# RGB_sensro_schematic.net
KiCad netlist of a schematic drawn in Altium Designer
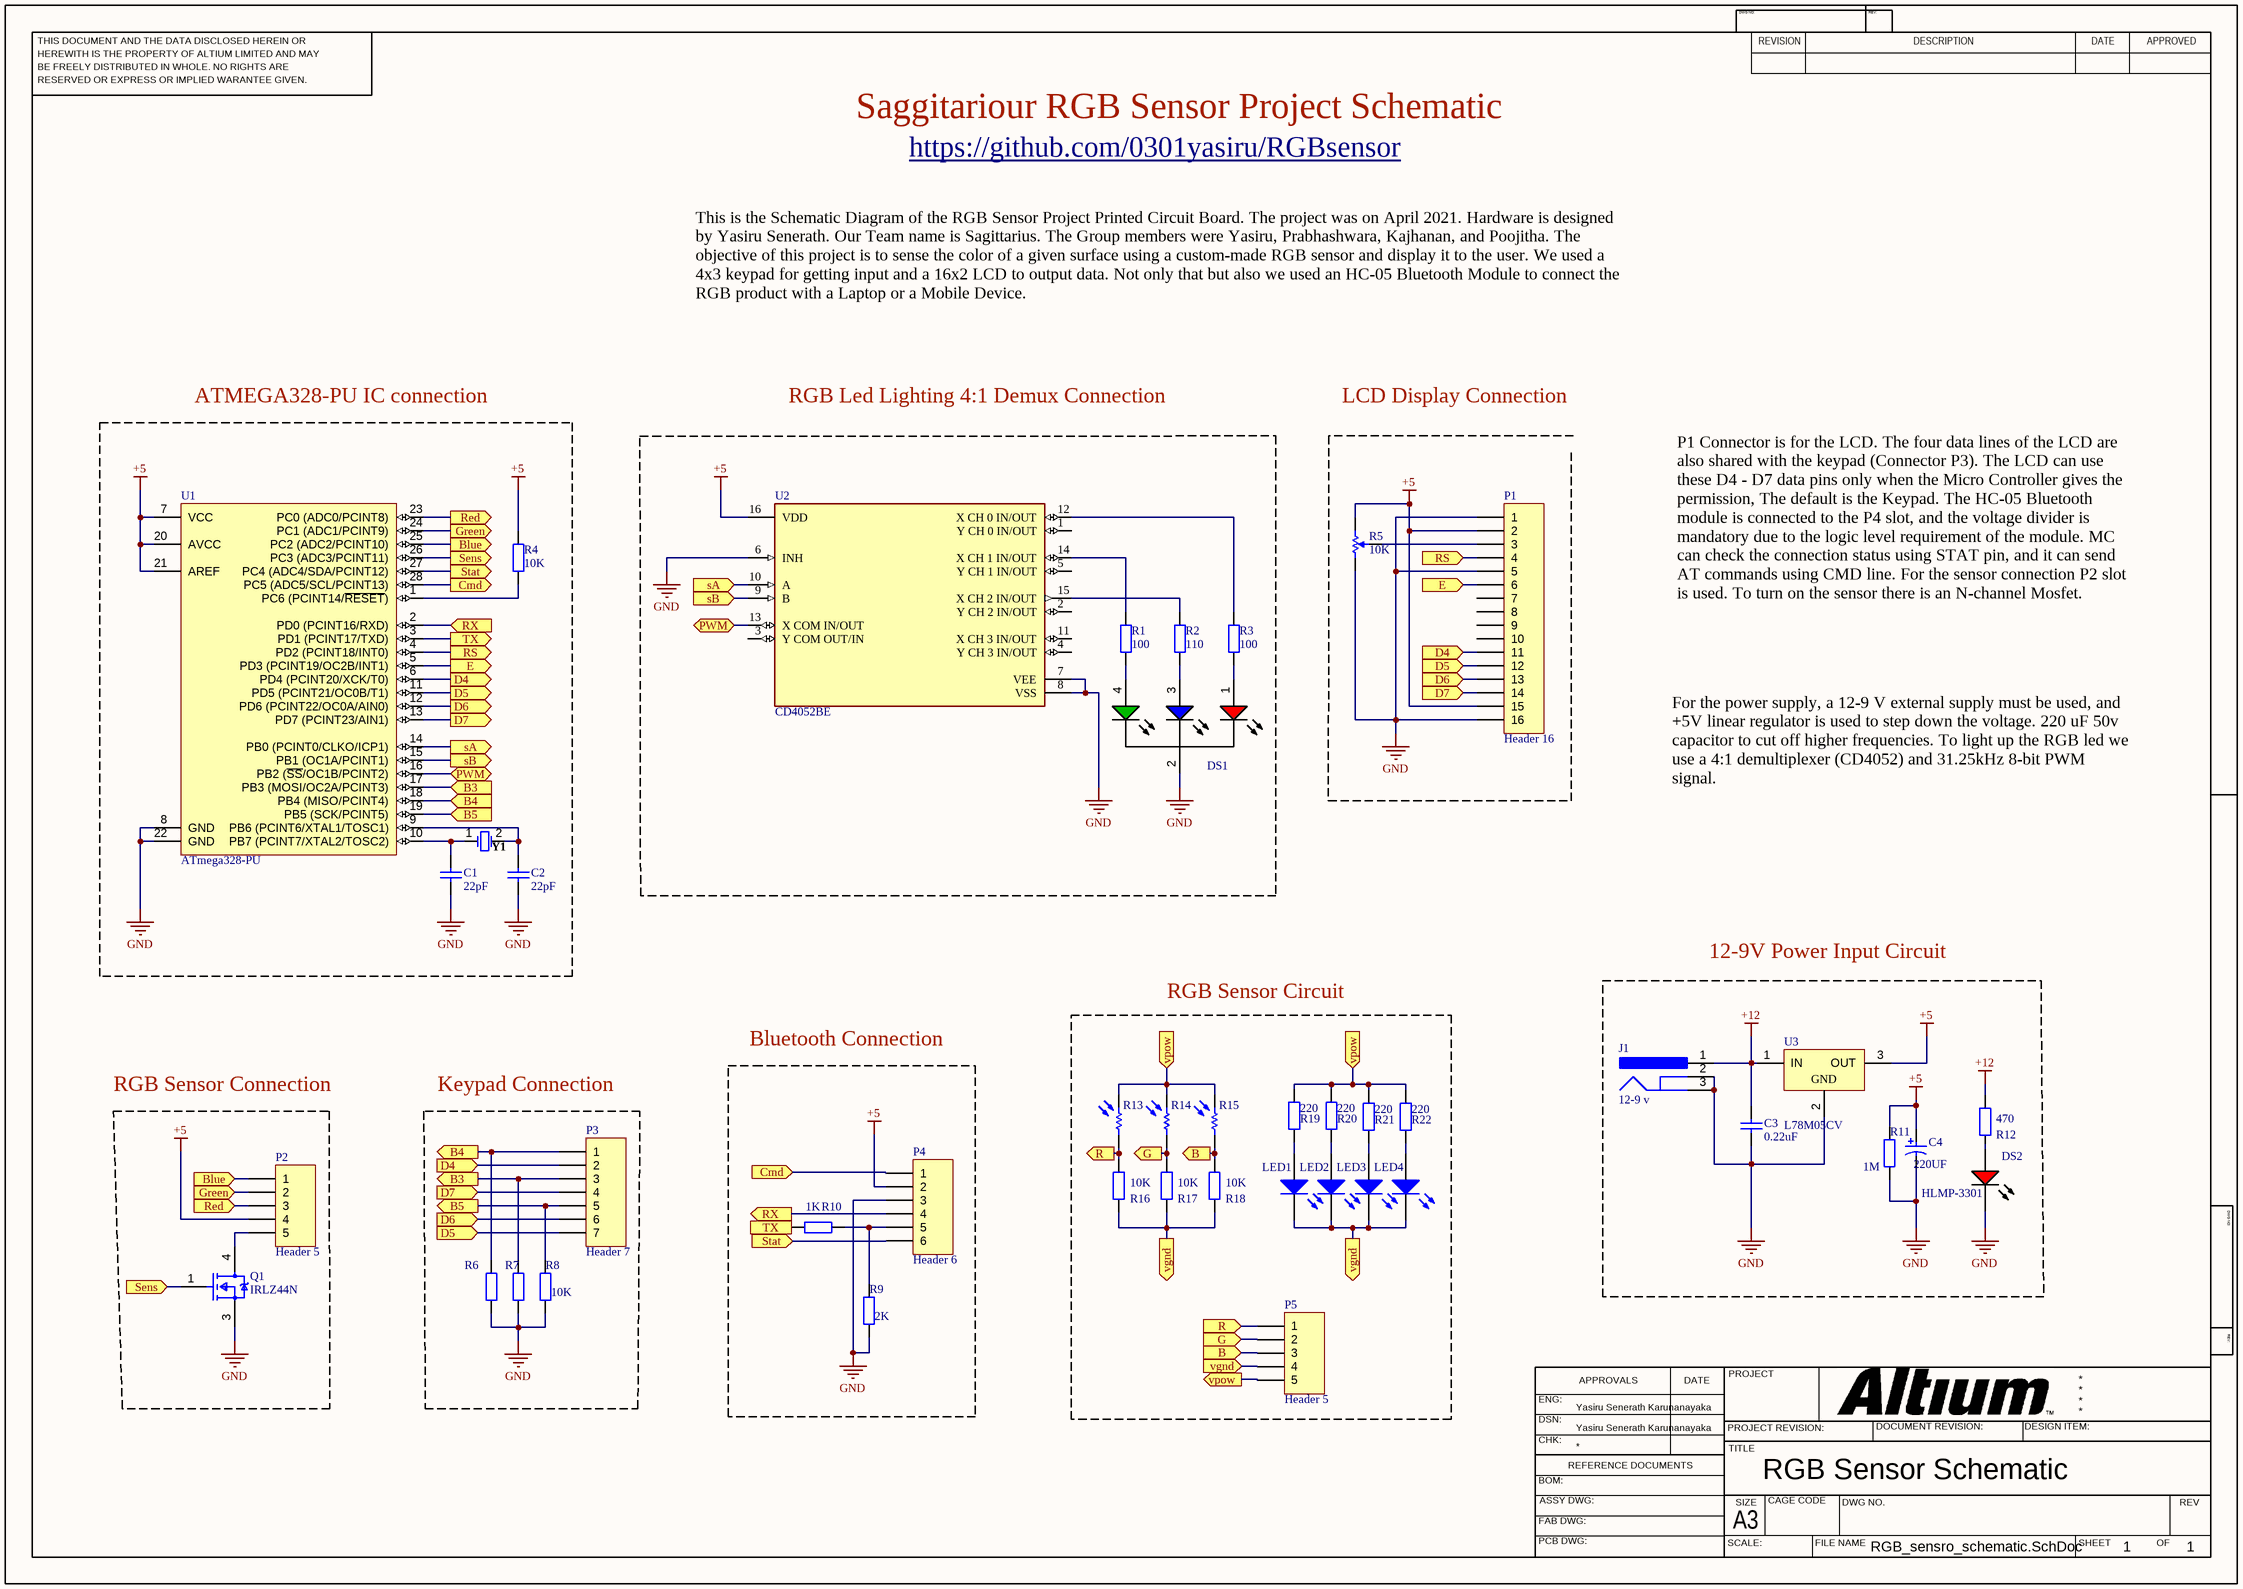
[diagram p0: RGB_sensro_schematic.SchDoc]

(export (version "E")
  (design (tool "Eeschema 10.0.6"))
  (components
    (comp (ref "C1")
      (value "22pF")
      (footprint "KEMT-C315-THT-2")
      (description "Capacitor, Ceramic, 22 pF, +/-10 %, 100 V, -55 to 125 degC, 2-Pin THD, RoHS, Bulk")
      (libsource (lib "Altium Content Vault") (part "CAP-NP-2"))
    )
    (comp (ref "C2")
      (value "22pF")
      (footprint "KEMT-C315-THT-2")
      (description "Capacitor, Ceramic, 22 pF, +/-10 %, 100 V, -55 to 125 degC, 2-Pin THD, RoHS, Bulk")
      (libsource (lib "Altium Content Vault") (part "CAP-NP-2"))
    )
    (comp (ref "C3")
      (value "0.22uF")
      (footprint "KEMT-C315-THT-2")
      (description "Capacitor, Ceramic, 22 pF, +/-10 %, 100 V, -55 to 125 degC, 2-Pin THD, RoHS, Bulk")
      (libsource (lib "Altium Content Vault") (part "CAP-NP-2"))
    )
    (comp (ref "C4")
      (value "220UF")
      (footprint "PNSC-EEE-1HA221P_L")
      (fields (field (name "MANUFACTURER") "Panasonic"))
      (libsource (lib "Altium Content Vault") (part "CAP-P-2"))
    )
    (comp (ref "DS1")
      (value "~")
      (footprint "KING-WP154A4SUREQBFZGC_V")
      (description "Full Color LED Lamp, Dominant Wavelength RGB 630 / 525 / 465 nm, -40 to 85 degC, 4-Pin THD, RoHS")
      (fields (field (name "MANUFACTURER") "Kingbright"))
      (libsource (lib "Altium Content Vault") (part "LED-RGB-AKAA-4"))
    )
    (comp (ref "DS2")
      (value "HLMP-3301")
      (footprint "AVAG-HLMP-3301-2")
      (description "T-1 3/4 (5 mm) Diffused LED Lamp, 1.9 V, -40 to 100 degC, 2-Pin THD, RoHS, Bulk")
      (fields (field (name "MANUFACTURER") "Avago"))
      (libsource (lib "Altium Content Vault") (part "LED-RED-K1A2-2"))
    )
    (comp (ref "J1")
      (value "12-9 v")
      (footprint "LUMB-NEB21R_V")
      (description "Jack Socket, Body 14.5 x 9 mm, Height 11 mm, -20 to 70 degC, 3-Pin THD, RoHS, Bulk")
      (fields (field (name "MANUFACTURER") "Lumberg"))
      (libsource (lib "Altium Content Vault") (part "JACK-2CD3-RN"))
    )
    (comp (ref "LED1")
      (value "151053RS03000")
      (footprint "Type 5mm")
      (description "THT LED round mono-color waterclear,  WL-TMRW ,Red")
      (fields (field (name "MANUFACTURER") "Wuerth Elektronik"))
      (libsource (lib "Altium Content Vault") (part "WE-LED_K1A2-2"))
    )
    (comp (ref "LED2")
      (value "151053RS03000")
      (footprint "Type 5mm")
      (description "THT LED round mono-color waterclear,  WL-TMRW ,Red")
      (fields (field (name "MANUFACTURER") "Wuerth Elektronik"))
      (libsource (lib "Altium Content Vault") (part "WE-LED_K1A2-2"))
    )
    (comp (ref "LED3")
      (value "151053RS03000")
      (footprint "Type 5mm")
      (description "THT LED round mono-color waterclear,  WL-TMRW ,Red")
      (fields (field (name "MANUFACTURER") "Wuerth Elektronik"))
      (libsource (lib "Altium Content Vault") (part "WE-LED_K1A2-2"))
    )
    (comp (ref "LED4")
      (value "151053RS03000")
      (footprint "Type 5mm")
      (description "THT LED round mono-color waterclear,  WL-TMRW ,Red")
      (fields (field (name "MANUFACTURER") "Wuerth Elektronik"))
      (libsource (lib "Altium Content Vault") (part "WE-LED_K1A2-2"))
    )
    (comp (ref "P1")
      (value "Header 16")
      (footprint "HDR1X16")
      (description "Header, 16-Pin")
      (fields (field (name "PUBLISHER") "Altium Limited"))
      (libsource (lib "Miscellaneous Connectors") (part "Header 16"))
    )
    (comp (ref "P2")
      (value "Header 5")
      (footprint "HDR1X5")
      (description "Header, 5-Pin")
      (fields (field (name "PUBLISHER") "Altium Limited"))
      (libsource (lib "Miscellaneous Connectors") (part "Header 5"))
    )
    (comp (ref "P3")
      (value "Header 7")
      (footprint "HDR1X7")
      (description "Header, 7-Pin")
      (fields (field (name "PUBLISHER") "Altium Limited"))
      (libsource (lib "Miscellaneous Connectors") (part "Header 7"))
    )
    (comp (ref "P4")
      (value "Header 6")
      (footprint "HDR1X6")
      (description "Header, 6-Pin")
      (fields (field (name "PUBLISHER") "Altium Limited"))
      (libsource (lib "Miscellaneous Connectors") (part "Header 6"))
    )
    (comp (ref "P5")
      (value "Header 5")
      (footprint "HDR1X5")
      (description "Header, 5-Pin")
      (fields (field (name "PUBLISHER") "Altium Limited"))
      (libsource (lib "Miscellaneous Connectors") (part "Header 5"))
    )
    (comp (ref "Q1")
      (value "IRLZ44N")
      (footprint "FP-PG-TO263-3-MFG")
      (description "MOSFET N-CH 55V 47A D2PAK")
      (libsource (lib "Altium Content Vault") (part "cdf1c68f84cb049e5ebc85739c3fcf6"))
    )
    (comp (ref "R1")
      (value "100")
      (footprint "AXIAL-0.4")
      (description "Resistor")
      (fields (field (name "PUBLISHER") "Altium Limited"))
      (libsource (lib "Miscellaneous Devices") (part "Res2"))
    )
    (comp (ref "R2")
      (value "110")
      (footprint "AXIAL-0.4")
      (description "Resistor")
      (fields (field (name "PUBLISHER") "Altium Limited"))
      (libsource (lib "Miscellaneous Devices") (part "Res2"))
    )
    (comp (ref "R3")
      (value "100")
      (footprint "AXIAL-0.4")
      (description "Resistor")
      (fields (field (name "PUBLISHER") "Altium Limited"))
      (libsource (lib "Miscellaneous Devices") (part "Res2"))
    )
    (comp (ref "R4")
      (value "10K")
      (footprint "AXIAL-0.4")
      (description "Resistor")
      (fields (field (name "PUBLISHER") "Altium Limited"))
      (libsource (lib "Miscellaneous Devices") (part "Res2"))
    )
    (comp (ref "R5")
      (value "10K")
      (footprint "BOUR-TC33X-2_V")
      (description "Trimming Potentiometer, 10000 Ohm, -40 to 100 degC, 3-Pin SMD, RoHS, Tape and Reel")
      (fields (field (name "TOLERANCE") "25%") (field (name "MANUFACTURER") "Bourns"))
      (libsource (lib "Altium Content Vault") (part "RES-ADJ-3_A"))
    )
    (comp (ref "R6")
      (value "10K")
      (footprint "AXIAL-0.4")
      (description "Resistor")
      (fields (field (name "PUBLISHER") "Altium Limited"))
      (libsource (lib "Miscellaneous Devices") (part "Res2"))
    )
    (comp (ref "R7")
      (value "10K")
      (footprint "AXIAL-0.4")
      (description "Resistor")
      (fields (field (name "PUBLISHER") "Altium Limited"))
      (libsource (lib "Miscellaneous Devices") (part "Res2"))
    )
    (comp (ref "R8")
      (value "10K")
      (footprint "AXIAL-0.4")
      (description "Resistor")
      (fields (field (name "PUBLISHER") "Altium Limited"))
      (libsource (lib "Miscellaneous Devices") (part "Res2"))
    )
    (comp (ref "R9")
      (value "2K")
      (footprint "AXIAL-0.4")
      (description "Resistor")
      (fields (field (name "PUBLISHER") "Altium Limited"))
      (libsource (lib "Miscellaneous Devices") (part "Res2"))
    )
    (comp (ref "R10")
      (value "1K")
      (footprint "AXIAL-0.4")
      (description "Resistor")
      (fields (field (name "PUBLISHER") "Altium Limited"))
      (libsource (lib "") (part "Res2_1"))
    )
    (comp (ref "R11")
      (value "1M")
      (footprint "AXIAL-0.4")
      (description "Resistor")
      (fields (field (name "PUBLISHER") "Altium Limited"))
      (libsource (lib "Miscellaneous Devices") (part "Res2"))
    )
    (comp (ref "R12")
      (value "470")
      (footprint "AXIAL-0.4")
      (description "Resistor")
      (fields (field (name "PUBLISHER") "Altium Limited"))
      (libsource (lib "Miscellaneous Devices") (part "Res2"))
    )
    (comp (ref "R13")
      (value "VT90N1")
      (footprint "EXCE-VT90N1")
      (description "Photoconductive Resistor, 200 kOhm, 100 V, 80 mW, -40 to 75 degC, 2-Pin THD, RoHS")
      (fields (field (name "MANUFACTURER") "Excelitas Technology"))
      (libsource (lib "Altium Content Vault") (part "PHOTO-RES-2"))
    )
    (comp (ref "R14")
      (value "VT90N1")
      (footprint "EXCE-VT90N1")
      (description "Photoconductive Resistor, 200 kOhm, 100 V, 80 mW, -40 to 75 degC, 2-Pin THD, RoHS")
      (fields (field (name "MANUFACTURER") "Excelitas Technology"))
      (libsource (lib "Altium Content Vault") (part "PHOTO-RES-2"))
    )
    (comp (ref "R15")
      (value "VT90N1")
      (footprint "EXCE-VT90N1")
      (description "Photoconductive Resistor, 200 kOhm, 100 V, 80 mW, -40 to 75 degC, 2-Pin THD, RoHS")
      (fields (field (name "MANUFACTURER") "Excelitas Technology"))
      (libsource (lib "Altium Content Vault") (part "PHOTO-RES-2"))
    )
    (comp (ref "R16")
      (value "10K")
      (footprint "AXIAL-0.4")
      (description "Resistor")
      (fields (field (name "PUBLISHER") "Altium Limited"))
      (libsource (lib "Miscellaneous Devices") (part "Res2"))
    )
    (comp (ref "R17")
      (value "10K")
      (footprint "AXIAL-0.4")
      (description "Resistor")
      (fields (field (name "PUBLISHER") "Altium Limited"))
      (libsource (lib "Miscellaneous Devices") (part "Res2"))
    )
    (comp (ref "R18")
      (value "10K")
      (footprint "AXIAL-0.4")
      (description "Resistor")
      (fields (field (name "PUBLISHER") "Altium Limited"))
      (libsource (lib "Miscellaneous Devices") (part "Res2"))
    )
    (comp (ref "R19")
      (value "220")
      (footprint "AXIAL-0.4")
      (description "Resistor")
      (fields (field (name "PUBLISHER") "Altium Limited"))
      (libsource (lib "Miscellaneous Devices") (part "Res2"))
    )
    (comp (ref "R20")
      (value "220")
      (footprint "AXIAL-0.4")
      (description "Resistor")
      (fields (field (name "PUBLISHER") "Altium Limited"))
      (libsource (lib "Miscellaneous Devices") (part "Res2"))
    )
    (comp (ref "R21")
      (value "220")
      (footprint "AXIAL-0.4")
      (description "Resistor")
      (fields (field (name "PUBLISHER") "Altium Limited"))
      (libsource (lib "Miscellaneous Devices") (part "Res2"))
    )
    (comp (ref "R22")
      (value "220")
      (footprint "AXIAL-0.4")
      (description "Resistor")
      (fields (field (name "PUBLISHER") "Altium Limited"))
      (libsource (lib "Miscellaneous Devices") (part "Res2"))
    )
    (comp (ref "U1")
      (value "ATmega328-PU")
      (footprint "28P3")
      (libsource (lib "Altium Content Vault") (part "MC-8B-ATM48-IL28"))
    )
    (comp (ref "U2")
      (value "CD4052BE")
      (footprint "FP-N0016A-MFG")
      (description "IC MUX/DEMUX DUAL 4X1 16DIP")
      (libsource (lib "Altium Content Vault") (part "f592c568caf548e7f28197573c85c05"))
    )
    (comp (ref "U3")
      (value "L78M05CV")
      (footprint "TO220")
      (description "Positive Voltage Regulator, 5V, 3-Pin TO-220")
      (libsource (lib "Altium Content Vault") (part "PM-REG-L4940-SIL3"))
    )
    (comp (ref "Y1")
      (value "FOXSLF/160-20")
      (footprint "FOX-FOXSLF160-20")
      (description "Resistance Weld Thru-Hole Crystal, 16 MHz, -20 to 70 degC, 2-Pin THD, RoHS, Bulk")
      (fields (field (name "TOLERANCE") "1%"))
      (libsource (lib "Altium Content Vault") (part "XTAL-1-2-2"))
    )
  )
  (nets
    (net (code "1") (name "+5") (class "Default")
      (node (ref "C4") (pin "1") (pinfunction "1_1") (pintype "passive"))
      (node (ref "P1") (pin "15") (pinfunction "15_15") (pintype "passive"))
      (node (ref "P1") (pin "2") (pinfunction "2_2") (pintype "passive"))
      (node (ref "P2") (pin "4") (pinfunction "4_4") (pintype "passive"))
      (node (ref "P4") (pin "2") (pinfunction "2_2") (pintype "passive"))
      (node (ref "R11") (pin "2") (pinfunction "2_2") (pintype "passive"))
      (node (ref "R4") (pin "2") (pinfunction "2_2") (pintype "passive"))
      (node (ref "R5") (pin "3") (pinfunction "3_3") (pintype "passive"))
      (node (ref "U1") (pin "20") (pinfunction "AVCC_20") (pintype "power_in"))
      (node (ref "U1") (pin "21") (pinfunction "AREF_21") (pintype "power_in"))
      (node (ref "U1") (pin "7") (pinfunction "VCC_7") (pintype "power_in"))
      (node (ref "U2") (pin "16") (pinfunction "VDD_16") (pintype "power_in"))
      (node (ref "U3") (pin "3") (pinfunction "OUT_3") (pintype "power_in"))
    )
    (net (code "2") (name "+12") (class "Default")
      (node (ref "C3") (pin "2") (pinfunction "2_2") (pintype "passive"))
      (node (ref "J1") (pin "1") (pinfunction "1_1") (pintype "passive"))
      (node (ref "R12") (pin "2") (pinfunction "2_2") (pintype "passive"))
      (node (ref "U3") (pin "1") (pinfunction "IN_1") (pintype "power_in"))
    )
    (net (code "3") (name "/B") (class "Default")
      (node (ref "P5") (pin "3") (pinfunction "3_3") (pintype "passive"))
      (node (ref "R15") (pin "1") (pinfunction "1_1") (pintype "passive"))
      (node (ref "R18") (pin "2") (pinfunction "2_2") (pintype "passive"))
    )
    (net (code "4") (name "/B3") (class "Default")
      (node (ref "P3") (pin "3") (pinfunction "3_3") (pintype "passive"))
      (node (ref "R7") (pin "2") (pinfunction "2_2") (pintype "passive"))
      (node (ref "U1") (pin "17") (pinfunction "PB3_(MOSI/OC2A/PCINT3)_17") (pintype "bidirectional"))
    )
    (net (code "5") (name "/B4") (class "Default")
      (node (ref "P3") (pin "1") (pinfunction "1_1") (pintype "passive"))
      (node (ref "R6") (pin "2") (pinfunction "2_2") (pintype "passive"))
      (node (ref "U1") (pin "18") (pinfunction "PB4_(MISO/PCINT4)_18") (pintype "bidirectional"))
    )
    (net (code "6") (name "/B5") (class "Default")
      (node (ref "P3") (pin "5") (pinfunction "5_5") (pintype "passive"))
      (node (ref "R8") (pin "2") (pinfunction "2_2") (pintype "passive"))
      (node (ref "U1") (pin "19") (pinfunction "PB5_(SCK/PCINT5)_19") (pintype "bidirectional"))
    )
    (net (code "7") (name "/Blue") (class "Default")
      (node (ref "P2") (pin "1") (pinfunction "1_1") (pintype "passive"))
      (node (ref "U1") (pin "25") (pinfunction "PC2_(ADC2/PCINT10)_25") (pintype "bidirectional"))
    )
    (net (code "8") (name "/Cmd") (class "Default")
      (node (ref "P4") (pin "1") (pinfunction "1_1") (pintype "passive"))
      (node (ref "U1") (pin "28") (pinfunction "PC5_(ADC5/SCL/PCINT13)_28") (pintype "bidirectional"))
    )
    (net (code "9") (name "/D4") (class "Default")
      (node (ref "P1") (pin "11") (pinfunction "11_11") (pintype "passive"))
      (node (ref "P3") (pin "2") (pinfunction "2_2") (pintype "passive"))
      (node (ref "U1") (pin "6") (pinfunction "PD4_(PCINT20/XCK/T0)_6") (pintype "bidirectional"))
    )
    (net (code "10") (name "/D5") (class "Default")
      (node (ref "P1") (pin "12") (pinfunction "12_12") (pintype "passive"))
      (node (ref "P3") (pin "7") (pinfunction "7_7") (pintype "passive"))
      (node (ref "U1") (pin "11") (pinfunction "PD5_(PCINT21/OC0B/T1)_11") (pintype "bidirectional"))
    )
    (net (code "11") (name "/D6") (class "Default")
      (node (ref "P1") (pin "13") (pinfunction "13_13") (pintype "passive"))
      (node (ref "P3") (pin "6") (pinfunction "6_6") (pintype "passive"))
      (node (ref "U1") (pin "12") (pinfunction "PD6_(PCINT22/OC0A/AIN0)_12") (pintype "bidirectional"))
    )
    (net (code "12") (name "/D7") (class "Default")
      (node (ref "P1") (pin "14") (pinfunction "14_14") (pintype "passive"))
      (node (ref "P3") (pin "4") (pinfunction "4_4") (pintype "passive"))
      (node (ref "U1") (pin "13") (pinfunction "PD7_(PCINT23/AIN1)_13") (pintype "bidirectional"))
    )
    (net (code "13") (name "/E") (class "Default")
      (node (ref "P1") (pin "6") (pinfunction "6_6") (pintype "passive"))
      (node (ref "U1") (pin "5") (pinfunction "PD3_(PCINT19/OC2B/INT1)_5") (pintype "bidirectional"))
    )
    (net (code "14") (name "/G") (class "Default")
      (node (ref "P5") (pin "2") (pinfunction "2_2") (pintype "passive"))
      (node (ref "R14") (pin "1") (pinfunction "1_1") (pintype "passive"))
      (node (ref "R17") (pin "2") (pinfunction "2_2") (pintype "passive"))
    )
    (net (code "15") (name "/Green") (class "Default")
      (node (ref "P2") (pin "2") (pinfunction "2_2") (pintype "passive"))
      (node (ref "U1") (pin "24") (pinfunction "PC1_(ADC1/PCINT9)_24") (pintype "bidirectional"))
    )
    (net (code "16") (name "/PWM") (class "Default")
      (node (ref "U1") (pin "16") (pinfunction "PB2_(~{SS}/OC1B/PCINT2)_16") (pintype "bidirectional"))
      (node (ref "U2") (pin "13") (pinfunction "X_COM_IN/OUT_13") (pintype "bidirectional"))
    )
    (net (code "17") (name "/R") (class "Default")
      (node (ref "P5") (pin "1") (pinfunction "1_1") (pintype "passive"))
      (node (ref "R13") (pin "1") (pinfunction "1_1") (pintype "passive"))
      (node (ref "R16") (pin "2") (pinfunction "2_2") (pintype "passive"))
    )
    (net (code "18") (name "/RS") (class "Default")
      (node (ref "P1") (pin "4") (pinfunction "4_4") (pintype "passive"))
      (node (ref "U1") (pin "4") (pinfunction "PD2_(PCINT18/INT0)_4") (pintype "bidirectional"))
    )
    (net (code "19") (name "/RX") (class "Default")
      (node (ref "P4") (pin "4") (pinfunction "4_4") (pintype "passive"))
      (node (ref "U1") (pin "2") (pinfunction "PD0_(PCINT16/RXD)_2") (pintype "bidirectional"))
    )
    (net (code "20") (name "/Red") (class "Default")
      (node (ref "P2") (pin "3") (pinfunction "3_3") (pintype "passive"))
      (node (ref "U1") (pin "23") (pinfunction "PC0_(ADC0/PCINT8)_23") (pintype "bidirectional"))
    )
    (net (code "21") (name "/Sens") (class "Default")
      (node (ref "Q1") (pin "1") (pinfunction "G_1") (pintype "passive"))
      (node (ref "U1") (pin "26") (pinfunction "PC3_(ADC3/PCINT11)_26") (pintype "bidirectional"))
    )
    (net (code "22") (name "/Stat") (class "Default")
      (node (ref "P4") (pin "6") (pinfunction "6_6") (pintype "passive"))
      (node (ref "U1") (pin "27") (pinfunction "PC4_(ADC4/SDA/PCINT12)_27") (pintype "bidirectional"))
    )
    (net (code "23") (name "/TX") (class "Default")
      (node (ref "R10") (pin "2") (pinfunction "2_2") (pintype "passive"))
      (node (ref "U1") (pin "3") (pinfunction "PD1_(PCINT17/TXD)_3") (pintype "bidirectional"))
    )
    (net (code "24") (name "/sA") (class "Default")
      (node (ref "U1") (pin "14") (pinfunction "PB0_(PCINT0/CLKO/ICP1)_14") (pintype "bidirectional"))
      (node (ref "U2") (pin "10") (pinfunction "A_10") (pintype "input"))
    )
    (net (code "25") (name "/sB") (class "Default")
      (node (ref "U1") (pin "15") (pinfunction "PB1_(OC1A/PCINT1)_15") (pintype "bidirectional"))
      (node (ref "U2") (pin "9") (pinfunction "B_9") (pintype "input"))
    )
    (net (code "26") (name "/vgnd") (class "Default")
      (node (ref "LED1") (pin "1") (pinfunction "K_1") (pintype "passive"))
      (node (ref "LED2") (pin "1") (pinfunction "K_1") (pintype "passive"))
      (node (ref "LED3") (pin "1") (pinfunction "K_1") (pintype "passive"))
      (node (ref "LED4") (pin "1") (pinfunction "K_1") (pintype "passive"))
      (node (ref "P5") (pin "4") (pinfunction "4_4") (pintype "passive"))
      (node (ref "R16") (pin "1") (pinfunction "1_1") (pintype "passive"))
      (node (ref "R17") (pin "1") (pinfunction "1_1") (pintype "passive"))
      (node (ref "R18") (pin "1") (pinfunction "1_1") (pintype "passive"))
    )
    (net (code "27") (name "/vpow") (class "Default")
      (node (ref "P5") (pin "5") (pinfunction "5_5") (pintype "passive"))
      (node (ref "R13") (pin "2") (pinfunction "2_2") (pintype "passive"))
      (node (ref "R14") (pin "2") (pinfunction "2_2") (pintype "passive"))
      (node (ref "R15") (pin "2") (pinfunction "2_2") (pintype "passive"))
      (node (ref "R19") (pin "2") (pinfunction "2_2") (pintype "passive"))
      (node (ref "R20") (pin "2") (pinfunction "2_2") (pintype "passive"))
      (node (ref "R21") (pin "2") (pinfunction "2_2") (pintype "passive"))
      (node (ref "R22") (pin "2") (pinfunction "2_2") (pintype "passive"))
    )
    (net (code "28") (name "GND") (class "Default")
      (node (ref "C1") (pin "1") (pinfunction "1_1") (pintype "passive"))
      (node (ref "C2") (pin "1") (pinfunction "1_1") (pintype "passive"))
      (node (ref "C3") (pin "1") (pinfunction "1_1") (pintype "passive"))
      (node (ref "C4") (pin "2") (pinfunction "2_2") (pintype "passive"))
      (node (ref "DS1") (pin "2") (pinfunction "CATHODE_2") (pintype "passive"))
      (node (ref "DS2") (pin "1") (pinfunction "K_1") (pintype "passive"))
      (node (ref "J1") (pin "2") (pinfunction "2_2") (pintype "passive"))
      (node (ref "J1") (pin "3") (pinfunction "3_3") (pintype "passive"))
      (node (ref "P1") (pin "1") (pinfunction "1_1") (pintype "passive"))
      (node (ref "P1") (pin "16") (pinfunction "16_16") (pintype "passive"))
      (node (ref "P1") (pin "5") (pinfunction "5_5") (pintype "passive"))
      (node (ref "P4") (pin "3") (pinfunction "3_3") (pintype "passive"))
      (node (ref "Q1") (pin "3") (pinfunction "S_3") (pintype "passive"))
      (node (ref "R11") (pin "1") (pinfunction "1_1") (pintype "passive"))
      (node (ref "R5") (pin "1") (pinfunction "1_1") (pintype "passive"))
      (node (ref "R6") (pin "1") (pinfunction "1_1") (pintype "passive"))
      (node (ref "R7") (pin "1") (pinfunction "1_1") (pintype "passive"))
      (node (ref "R8") (pin "1") (pinfunction "1_1") (pintype "passive"))
      (node (ref "R9") (pin "1") (pinfunction "1_1") (pintype "passive"))
      (node (ref "U1") (pin "22") (pinfunction "GND_22") (pintype "power_in"))
      (node (ref "U1") (pin "8") (pinfunction "GND_8") (pintype "power_in"))
      (node (ref "U2") (pin "6") (pinfunction "INH_6") (pintype "input"))
      (node (ref "U2") (pin "7") (pinfunction "VEE_7") (pintype "power_in"))
      (node (ref "U2") (pin "8") (pinfunction "VSS_8") (pintype "power_in"))
      (node (ref "U3") (pin "2") (pinfunction "GND_2") (pintype "power_in"))
    )
    (net (code "29") (name "Net-(DS1-BLUE)") (class "Default")
      (node (ref "DS1") (pin "3") (pinfunction "BLUE_3") (pintype "passive"))
      (node (ref "R2") (pin "1") (pinfunction "1_1") (pintype "passive"))
    )
    (net (code "30") (name "Net-(DS1-GREEN)") (class "Default")
      (node (ref "DS1") (pin "4") (pinfunction "GREEN_4") (pintype "passive"))
      (node (ref "R1") (pin "1") (pinfunction "1_1") (pintype "passive"))
    )
    (net (code "31") (name "Net-(DS1-RED)") (class "Default")
      (node (ref "DS1") (pin "1") (pinfunction "RED_1") (pintype "passive"))
      (node (ref "R3") (pin "1") (pinfunction "1_1") (pintype "passive"))
    )
    (net (code "32") (name "Net-(DS2-A)") (class "Default")
      (node (ref "DS2") (pin "2") (pinfunction "A_2") (pintype "passive"))
      (node (ref "R12") (pin "1") (pinfunction "1_1") (pintype "passive"))
    )
    (net (code "33") (name "Net-(LED1-A)") (class "Default")
      (node (ref "LED1") (pin "2") (pinfunction "A_2") (pintype "passive"))
      (node (ref "R19") (pin "1") (pinfunction "1_1") (pintype "passive"))
    )
    (net (code "34") (name "Net-(LED2-A)") (class "Default")
      (node (ref "LED2") (pin "2") (pinfunction "A_2") (pintype "passive"))
      (node (ref "R20") (pin "1") (pinfunction "1_1") (pintype "passive"))
    )
    (net (code "35") (name "Net-(LED3-A)") (class "Default")
      (node (ref "LED3") (pin "2") (pinfunction "A_2") (pintype "passive"))
      (node (ref "R21") (pin "1") (pinfunction "1_1") (pintype "passive"))
    )
    (net (code "36") (name "Net-(LED4-A)") (class "Default")
      (node (ref "LED4") (pin "2") (pinfunction "A_2") (pintype "passive"))
      (node (ref "R22") (pin "1") (pinfunction "1_1") (pintype "passive"))
    )
    (net (code "37") (name "Net-(P1-Pad3)") (class "Default")
      (node (ref "P1") (pin "3") (pinfunction "3_3") (pintype "passive"))
      (node (ref "R5") (pin "2") (pinfunction "2_2") (pintype "passive"))
    )
    (net (code "38") (name "Net-(P4-Pad5)") (class "Default")
      (node (ref "P4") (pin "5") (pinfunction "5_5") (pintype "passive"))
      (node (ref "R10") (pin "1") (pinfunction "1_1") (pintype "passive"))
      (node (ref "R9") (pin "2") (pinfunction "2_2") (pintype "passive"))
    )
    (net (code "39") (name "Net-(Q1-D)") (class "Default")
      (node (ref "P2") (pin "5") (pinfunction "5_5") (pintype "passive"))
      (node (ref "Q1") (pin "4") (pinfunction "D_4") (pintype "passive"))
    )
    (net (code "40") (name "Net-(U1-PB6_(PCINT6{slash}XTAL1{slash}TOSC1))") (class "Default")
      (node (ref "C2") (pin "2") (pinfunction "2_2") (pintype "passive"))
      (node (ref "U1") (pin "9") (pinfunction "PB6_(PCINT6/XTAL1/TOSC1)_9") (pintype "bidirectional"))
      (node (ref "Y1") (pin "2") (pinfunction "2_2") (pintype "passive"))
    )
    (net (code "41") (name "Net-(U1-PB7_(PCINT7{slash}XTAL2{slash}TOSC2))") (class "Default")
      (node (ref "C1") (pin "2") (pinfunction "2_2") (pintype "passive"))
      (node (ref "U1") (pin "10") (pinfunction "PB7_(PCINT7/XTAL2/TOSC2)_10") (pintype "bidirectional"))
      (node (ref "Y1") (pin "1") (pinfunction "1_1") (pintype "passive"))
    )
    (net (code "42") (name "Net-(U1-PC6_(PCINT14{slash}~{RESET}))") (class "Default")
      (node (ref "R4") (pin "1") (pinfunction "1_1") (pintype "passive"))
      (node (ref "U1") (pin "1") (pinfunction "PC6_(PCINT14/~{RESET})_1") (pintype "bidirectional"))
    )
    (net (code "43") (name "Net-(U2-X_CH_0_IN{slash}OUT)") (class "Default")
      (node (ref "R3") (pin "2") (pinfunction "2_2") (pintype "passive"))
      (node (ref "U2") (pin "12") (pinfunction "X_CH_0_IN/OUT_12") (pintype "bidirectional"))
    )
    (net (code "44") (name "Net-(U2-X_CH_1_IN{slash}OUT)") (class "Default")
      (node (ref "R1") (pin "2") (pinfunction "2_2") (pintype "passive"))
      (node (ref "U2") (pin "14") (pinfunction "X_CH_1_IN/OUT_14") (pintype "bidirectional"))
    )
    (net (code "45") (name "Net-(U2-X_CH_2_IN{slash}OUT)") (class "Default")
      (node (ref "R2") (pin "2") (pinfunction "2_2") (pintype "passive"))
      (node (ref "U2") (pin "15") (pinfunction "X_CH_2_IN/OUT_15") (pintype "output"))
    )
    (net (code "46") (name "unconnected-(P1-Pad7)") (class "Default")
      (node (ref "P1") (pin "7") (pinfunction "7_7") (pintype "passive"))
    )
    (net (code "47") (name "unconnected-(P1-Pad8)") (class "Default")
      (node (ref "P1") (pin "8") (pinfunction "8_8") (pintype "passive"))
    )
    (net (code "48") (name "unconnected-(P1-Pad9)") (class "Default")
      (node (ref "P1") (pin "9") (pinfunction "9_9") (pintype "passive"))
    )
    (net (code "49") (name "unconnected-(P1-Pad10)") (class "Default")
      (node (ref "P1") (pin "10") (pinfunction "10_10") (pintype "passive"))
    )
    (net (code "50") (name "unconnected-(U2-X_CH_3_IN{slash}OUT-Pad11)") (class "Default")
      (node (ref "U2") (pin "11") (pinfunction "X_CH_3_IN/OUT_11") (pintype "bidirectional"))
    )
    (net (code "51") (name "unconnected-(U2-Y_CH_0_IN{slash}OUT-Pad1)") (class "Default")
      (node (ref "U2") (pin "1") (pinfunction "Y_CH_0_IN/OUT_1") (pintype "bidirectional"))
    )
    (net (code "52") (name "unconnected-(U2-Y_CH_1_IN{slash}OUT-Pad5)") (class "Default")
      (node (ref "U2") (pin "5") (pinfunction "Y_CH_1_IN/OUT_5") (pintype "bidirectional"))
    )
    (net (code "53") (name "unconnected-(U2-Y_CH_2_IN{slash}OUT-Pad2)") (class "Default")
      (node (ref "U2") (pin "2") (pinfunction "Y_CH_2_IN/OUT_2") (pintype "bidirectional"))
    )
    (net (code "54") (name "unconnected-(U2-Y_CH_3_IN{slash}OUT-Pad4)") (class "Default")
      (node (ref "U2") (pin "4") (pinfunction "Y_CH_3_IN/OUT_4") (pintype "bidirectional"))
    )
    (net (code "55") (name "unconnected-(U2-Y_COM_OUT{slash}IN-Pad3)") (class "Default")
      (node (ref "U2") (pin "3") (pinfunction "Y_COM_OUT/IN_3") (pintype "bidirectional"))
    )
  )
)
